# tip120_controller.net
KiCad netlist of a schematic drawn in EAGLE
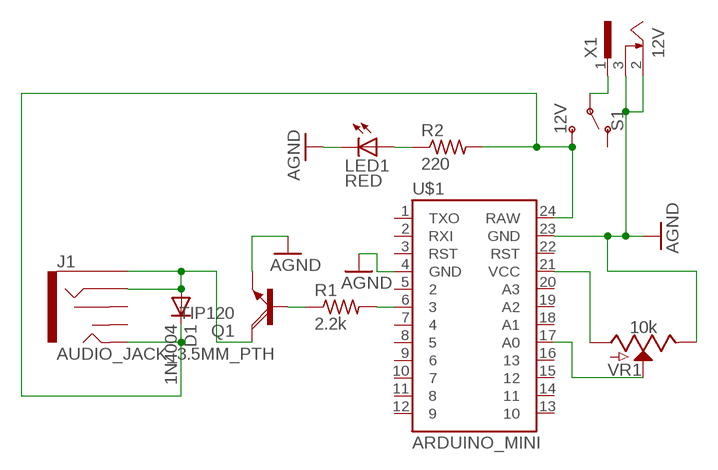
[diagram p0: schematic, sheet 1]

(export (version "E")
  (design (tool "Eeschema 10.0.6"))
  (components
    (comp (ref "D1")
      (value "1N4004")
      (footprint "eagle-import:DO41-10")
      (libsource (lib "eagle-import") (part "1N4004"))
    )
    (comp (ref "J1")
      (value "AUDIO_JACK_3.5MM_PTH")
      (footprint "eagle-import:AUDIO-JACK")
      (libsource (lib "eagle-import") (part "AUDIO_JACK_3.5MM_PTH"))
    )
    (comp (ref "LED1")
      (value "RED")
      (footprint "eagle-import:LED5MM")
      (libsource (lib "eagle-import") (part "LED5MM"))
    )
    (comp (ref "Q1")
      (value "TIP120")
      (footprint "eagle-import:TO220AH")
      (libsource (lib "eagle-import") (part "TIP120"))
    )
    (comp (ref "R1")
      (value "2.2k")
      (footprint "eagle-import:0204V")
      (libsource (lib "eagle-import") (part "R-US_0204/2V"))
    )
    (comp (ref "R2")
      (value "220")
      (footprint "eagle-import:0204V")
      (libsource (lib "eagle-import") (part "R-US_0204/2V"))
    )
    (comp (ref "S1")
      (value "12V")
      (footprint "eagle-import:SWITCH_SPDT_PTH_11.6X4.0MM_KIT")
      (libsource (lib "eagle-import") (part "SWITCH-SPDT-PTH-11.6X4.0MM-KIT"))
    )
    (comp (ref "U$1")
      (value "ARDUINO_MINI")
      (footprint "eagle-import:ARDUINO_MINI")
      (libsource (lib "eagle-import") (part "ARDUINO_MINI"))
    )
    (comp (ref "VR1")
      (value "10k")
      (footprint "eagle-import:POT-PTH-ALPS")
      (libsource (lib "eagle-import") (part "POTENTIOMETER-PTH-9MM-1/20W-20%"))
    )
    (comp (ref "X1")
      (value "12V")
      (footprint "eagle-import:SCD-014-A")
      (libsource (lib "eagle-import") (part "SCD-014A"))
    )
  )
  (nets
    (net (code "1") (name "AGND") (class "Default")
      (node (ref "LED1") (pin "K") (pinfunction "C_K") (pintype "passive"))
      (node (ref "Q1") (pin "E") (pinfunction "E_E") (pintype "passive"))
      (node (ref "U$1") (pin "23") (pinfunction "GND_23") (pintype "bidirectional"))
      (node (ref "U$1") (pin "4") (pinfunction "GND_4") (pintype "bidirectional"))
      (node (ref "VR1") (pin "P$1") (pinfunction "E_P$1") (pintype "passive"))
      (node (ref "X1") (pin "2") (pinfunction "2_2") (pintype "passive"))
      (node (ref "X1") (pin "3") (pinfunction "3_3") (pintype "passive"))
    )
    (net (code "2") (name "Net-(D1-PadA)") (class "Default")
      (node (ref "D1") (pin "A") (pinfunction "A_A") (pintype "passive"))
      (node (ref "J1") (pin "RING") (pinfunction "RING_RING") (pintype "bidirectional"))
      (node (ref "J1") (pin "SLEEVE") (pinfunction "SLEEVE_SLEEVE") (pintype "bidirectional"))
      (node (ref "Q1") (pin "C") (pinfunction "C_C") (pintype "passive"))
    )
    (net (code "3") (name "Net-(LED1-PadA)") (class "Default")
      (node (ref "LED1") (pin "A") (pinfunction "A_A") (pintype "passive"))
      (node (ref "R2") (pin "1") (pinfunction "1_1") (pintype "passive"))
    )
    (net (code "4") (name "Net-(Q1-PadB)") (class "Default")
      (node (ref "Q1") (pin "B") (pinfunction "B_B") (pintype "passive"))
      (node (ref "R1") (pin "1") (pinfunction "1_1") (pintype "passive"))
    )
    (net (code "5") (name "Net-(S1-P)") (class "Default")
      (node (ref "S1") (pin "2") (pinfunction "P_2") (pintype "passive"))
      (node (ref "X1") (pin "1") (pinfunction "1_1") (pintype "passive"))
    )
    (net (code "6") (name "Net-(S1-S)") (class "Default")
      (node (ref "D1") (pin "C") (pinfunction "C_C") (pintype "passive"))
      (node (ref "J1") (pin "TIP") (pinfunction "TIP_TIP") (pintype "bidirectional"))
      (node (ref "R2") (pin "2") (pinfunction "2_2") (pintype "passive"))
      (node (ref "S1") (pin "3") (pinfunction "S_3") (pintype "passive"))
      (node (ref "U$1") (pin "24") (pinfunction "RAW_24") (pintype "bidirectional"))
    )
    (net (code "7") (name "Net-(U$1-3)") (class "Default")
      (node (ref "R1") (pin "2") (pinfunction "2_2") (pintype "passive"))
      (node (ref "U$1") (pin "6") (pinfunction "3_6") (pintype "bidirectional"))
    )
    (net (code "8") (name "Net-(U$1-A0)") (class "Default")
      (node (ref "U$1") (pin "17") (pinfunction "A0_17") (pintype "bidirectional"))
      (node (ref "VR1") (pin "P$2") (pinfunction "S_P$2") (pintype "passive"))
    )
    (net (code "9") (name "Net-(U$1-VCC)") (class "Default")
      (node (ref "U$1") (pin "21") (pinfunction "VCC_21") (pintype "bidirectional"))
      (node (ref "VR1") (pin "P$3") (pinfunction "A_P$3") (pintype "passive"))
    )
    (net (code "10") (name "unconnected-(J1-PadRSH)") (class "Default")
      (node (ref "J1") (pin "RSH") (pinfunction "RSH_RSH") (pintype "bidirectional"))
    )
    (net (code "11") (name "unconnected-(J1-PadTSH)") (class "Default")
      (node (ref "J1") (pin "TSH") (pinfunction "TSH_TSH") (pintype "bidirectional"))
    )
    (net (code "12") (name "unconnected-(S1-O-Pad1)") (class "Default")
      (node (ref "S1") (pin "1") (pinfunction "O_1") (pintype "passive"))
    )
    (net (code "13") (name "unconnected-(U$1-2-Pad5)") (class "Default")
      (node (ref "U$1") (pin "5") (pinfunction "2_5") (pintype "bidirectional"))
    )
    (net (code "14") (name "unconnected-(U$1-4-Pad7)") (class "Default")
      (node (ref "U$1") (pin "7") (pinfunction "4_7") (pintype "bidirectional"))
    )
    (net (code "15") (name "unconnected-(U$1-5-Pad8)") (class "Default")
      (node (ref "U$1") (pin "8") (pinfunction "5_8") (pintype "bidirectional"))
    )
    (net (code "16") (name "unconnected-(U$1-6-Pad9)") (class "Default")
      (node (ref "U$1") (pin "9") (pinfunction "6_9") (pintype "bidirectional"))
    )
    (net (code "17") (name "unconnected-(U$1-7-Pad10)") (class "Default")
      (node (ref "U$1") (pin "10") (pinfunction "7_10") (pintype "bidirectional"))
    )
    (net (code "18") (name "unconnected-(U$1-8-Pad11)") (class "Default")
      (node (ref "U$1") (pin "11") (pinfunction "8_11") (pintype "bidirectional"))
    )
    (net (code "19") (name "unconnected-(U$1-9-Pad12)") (class "Default")
      (node (ref "U$1") (pin "12") (pinfunction "9_12") (pintype "bidirectional"))
    )
    (net (code "20") (name "unconnected-(U$1-10-Pad13)") (class "Default")
      (node (ref "U$1") (pin "13") (pinfunction "10_13") (pintype "bidirectional"))
    )
    (net (code "21") (name "unconnected-(U$1-11-Pad14)") (class "Default")
      (node (ref "U$1") (pin "14") (pinfunction "11_14") (pintype "bidirectional"))
    )
    (net (code "22") (name "unconnected-(U$1-12-Pad15)") (class "Default")
      (node (ref "U$1") (pin "15") (pinfunction "12_15") (pintype "bidirectional"))
    )
    (net (code "23") (name "unconnected-(U$1-13-Pad16)") (class "Default")
      (node (ref "U$1") (pin "16") (pinfunction "13_16") (pintype "bidirectional"))
    )
    (net (code "24") (name "unconnected-(U$1-A1-Pad18)") (class "Default")
      (node (ref "U$1") (pin "18") (pinfunction "A1_18") (pintype "bidirectional"))
    )
    (net (code "25") (name "unconnected-(U$1-A2-Pad19)") (class "Default")
      (node (ref "U$1") (pin "19") (pinfunction "A2_19") (pintype "bidirectional"))
    )
    (net (code "26") (name "unconnected-(U$1-A3-Pad20)") (class "Default")
      (node (ref "U$1") (pin "20") (pinfunction "A3_20") (pintype "bidirectional"))
    )
    (net (code "27") (name "unconnected-(U$1-RST-Pad3)") (class "Default")
      (node (ref "U$1") (pin "3") (pinfunction "RST_3") (pintype "bidirectional"))
    )
    (net (code "28") (name "unconnected-(U$1-RST-Pad22)") (class "Default")
      (node (ref "U$1") (pin "22") (pinfunction "RST_22") (pintype "bidirectional"))
    )
    (net (code "29") (name "unconnected-(U$1-RXI-Pad2)") (class "Default")
      (node (ref "U$1") (pin "2") (pinfunction "RXI_2") (pintype "bidirectional"))
    )
    (net (code "30") (name "unconnected-(U$1-TXO-Pad1)") (class "Default")
      (node (ref "U$1") (pin "1") (pinfunction "TXO_1") (pintype "bidirectional"))
    )
  )
)
